# ADP1612_5V_OUT.net
KiCad netlist of a schematic drawn in EAGLE
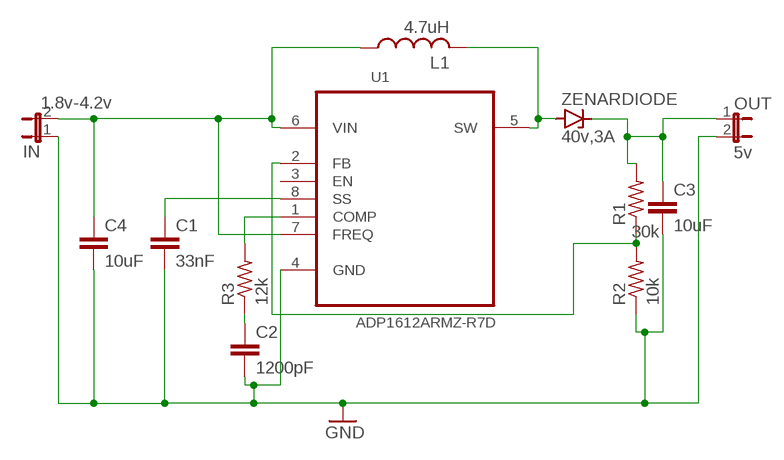
[diagram p0: schematic, sheet 1]

(export (version "E")
  (design (tool "Eeschema 10.0.6"))
  (components
    (comp (ref "C1")
      (value "33nF")
      (footprint "eagle-import:C5B3")
      (libsource (lib "eagle-import") (part "C5/3"))
    )
    (comp (ref "C2")
      (value "1200pF")
      (footprint "eagle-import:C5B3")
      (libsource (lib "eagle-import") (part "C5/3"))
    )
    (comp (ref "C3")
      (value "10uF")
      (footprint "eagle-import:C5B3")
      (libsource (lib "eagle-import") (part "C5/3"))
    )
    (comp (ref "C4")
      (value "10uF")
      (footprint "eagle-import:C5B3")
      (libsource (lib "eagle-import") (part "C5/3"))
    )
    (comp (ref "IN")
      (value "1.8v-4.2v")
      (footprint "eagle-import:JP1")
      (libsource (lib "eagle-import") (part "JP1E"))
    )
    (comp (ref "L1")
      (value "4.7uH")
      (footprint "eagle-import:0207_10")
      (libsource (lib "eagle-import") (part "L-US0207/10"))
    )
    (comp (ref "OUT")
      (value "5v")
      (footprint "eagle-import:JP1")
      (libsource (lib "eagle-import") (part "JP1E"))
    )
    (comp (ref "R1")
      (value "30k")
      (footprint "eagle-import:0207_7")
      (libsource (lib "eagle-import") (part "R-US_0207/7"))
    )
    (comp (ref "R2")
      (value "10k")
      (footprint "eagle-import:0207_7")
      (libsource (lib "eagle-import") (part "R-US_0207/7"))
    )
    (comp (ref "R3")
      (value "12k")
      (footprint "eagle-import:0207_7")
      (libsource (lib "eagle-import") (part "R-US_0207/7"))
    )
    (comp (ref "U1")
      (value "ADP1612ARMZ-R7D")
      (footprint "eagle-import:SOIC-08")
      (fields
        (field (name "DIGI-KEY_PART_NUMBER") "ADP1612ARMZ-R7CT-ND")
        (field (name "MF") "Analog Devices")
        (field (name "MP") "ADP1612ARMZ-R7")
      )
      (libsource (lib "eagle-import") (part "ADP1612ARMZ-R7D"))
    )
    (comp (ref "ZENARDIODE")
      (value "40v,3A")
      (footprint "eagle-import:DO35Z10")
      (libsource (lib "eagle-import") (part "BZX55"))
    )
  )
  (nets
    (net (code "1") (name "GND") (class "Default")
      (node (ref "C1") (pin "2") (pinfunction "2_2") (pintype "passive"))
      (node (ref "C2") (pin "2") (pinfunction "2_2") (pintype "passive"))
      (node (ref "C3") (pin "2") (pinfunction "2_2") (pintype "passive"))
      (node (ref "C4") (pin "2") (pinfunction "2_2") (pintype "passive"))
      (node (ref "IN") (pin "1") (pinfunction "1_1") (pintype "passive"))
      (node (ref "OUT") (pin "2") (pinfunction "2_2") (pintype "passive"))
      (node (ref "R2") (pin "1") (pinfunction "1_1") (pintype "passive"))
      (node (ref "U1") (pin "4") (pinfunction "GND_4") (pintype "passive"))
    )
    (net (code "2") (name "Net-(C2-Pad1)") (class "Default")
      (node (ref "C2") (pin "1") (pinfunction "1_1") (pintype "passive"))
      (node (ref "R3") (pin "1") (pinfunction "1_1") (pintype "passive"))
    )
    (net (code "3") (name "Net-(C3-Pad1)") (class "Default")
      (node (ref "C3") (pin "1") (pinfunction "1_1") (pintype "passive"))
      (node (ref "OUT") (pin "1") (pinfunction "1_1") (pintype "passive"))
      (node (ref "R1") (pin "2") (pinfunction "2_2") (pintype "passive"))
      (node (ref "ZENARDIODE") (pin "C") (pinfunction "C_C") (pintype "passive"))
    )
    (net (code "4") (name "Net-(U1-COMP)") (class "Default")
      (node (ref "R3") (pin "2") (pinfunction "2_2") (pintype "passive"))
      (node (ref "U1") (pin "1") (pinfunction "COMP_1") (pintype "passive"))
    )
    (net (code "5") (name "Net-(U1-FB)") (class "Default")
      (node (ref "R1") (pin "1") (pinfunction "1_1") (pintype "passive"))
      (node (ref "R2") (pin "2") (pinfunction "2_2") (pintype "passive"))
      (node (ref "U1") (pin "2") (pinfunction "FB_2") (pintype "input"))
    )
    (net (code "6") (name "Net-(U1-FREQ)") (class "Default")
      (node (ref "C4") (pin "1") (pinfunction "1_1") (pintype "passive"))
      (node (ref "IN") (pin "2") (pinfunction "2_2") (pintype "passive"))
      (node (ref "L1") (pin "1") (pinfunction "1_1") (pintype "passive"))
      (node (ref "U1") (pin "6") (pinfunction "VIN_6") (pintype "input"))
      (node (ref "U1") (pin "7") (pinfunction "FREQ_7") (pintype "input"))
    )
    (net (code "7") (name "Net-(U1-SS)") (class "Default")
      (node (ref "C1") (pin "1") (pinfunction "1_1") (pintype "passive"))
      (node (ref "U1") (pin "8") (pinfunction "SS_8") (pintype "input"))
    )
    (net (code "8") (name "Net-(U1-SW)") (class "Default")
      (node (ref "L1") (pin "2") (pinfunction "2_2") (pintype "passive"))
      (node (ref "U1") (pin "5") (pinfunction "SW_5") (pintype "output"))
      (node (ref "ZENARDIODE") (pin "A") (pinfunction "A_A") (pintype "passive"))
    )
    (net (code "9") (name "unconnected-(U1-EN-Pad3)") (class "Default")
      (node (ref "U1") (pin "3") (pinfunction "EN_3") (pintype "input"))
    )
  )
)
